# bldc_servo_controller_v1.net
KiCad netlist of a schematic drawn in EAGLE
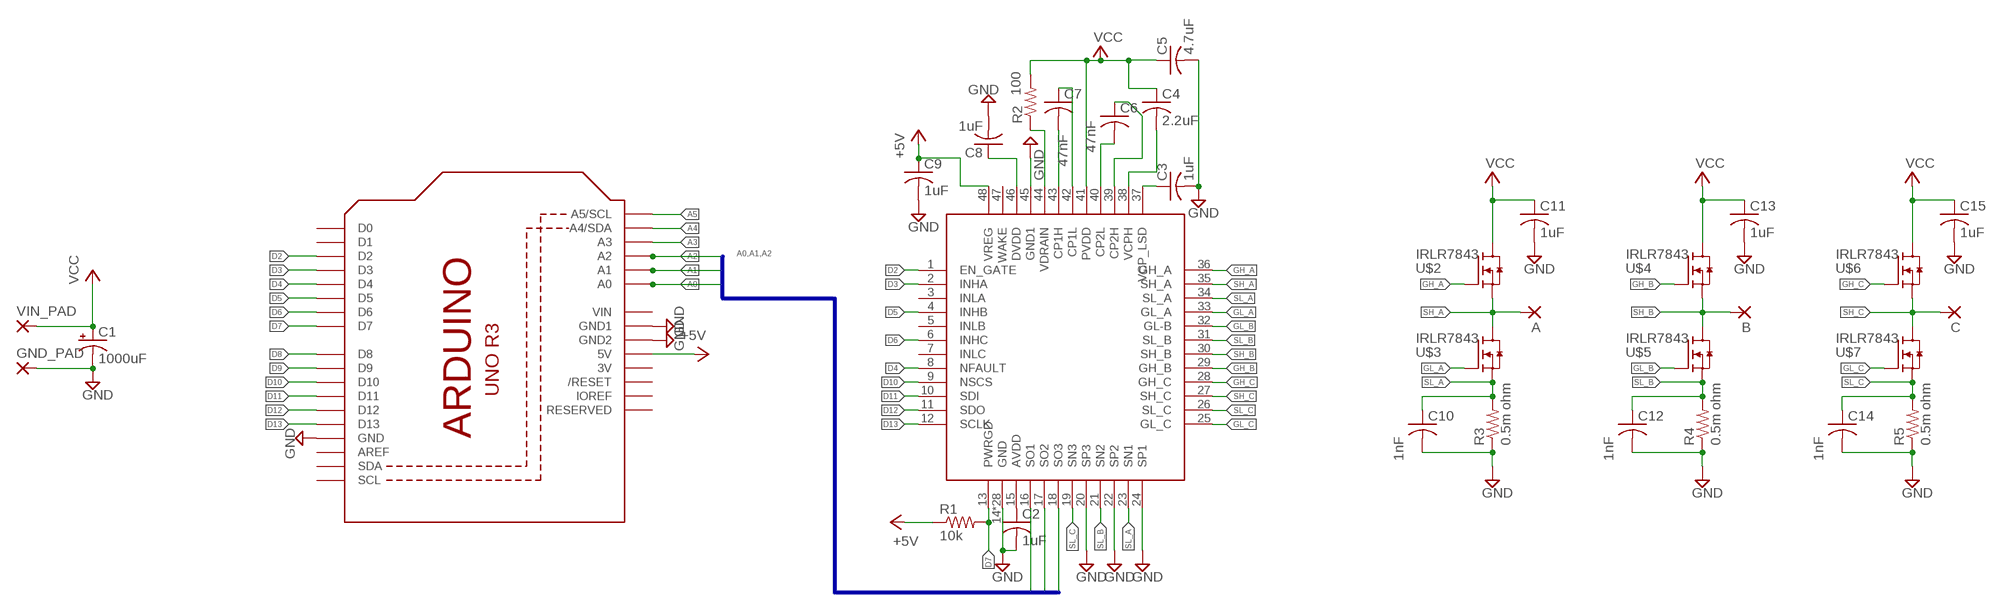
[diagram p0: schematic, sheet 1]

(export (version "E")
  (design (tool "Eeschema 10.0.6"))
  (components
    (comp (ref "A")
      (value "WIREPAD1,6/0,8")
      (footprint "eagle-import:1,6_0,8")
      (libsource (lib "eagle-import") (part "WIREPAD1,6/0,8"))
    )
    (comp (ref "B")
      (value "WIREPAD1,6/0,8")
      (footprint "eagle-import:1,6_0,8")
      (libsource (lib "eagle-import") (part "WIREPAD1,6/0,8"))
    )
    (comp (ref "C")
      (value "WIREPAD1,6/0,8")
      (footprint "eagle-import:1,6_0,8")
      (libsource (lib "eagle-import") (part "WIREPAD1,6/0,8"))
    )
    (comp (ref "C1")
      (value "1000uF")
      (footprint "eagle-import:E3,5-10")
      (libsource (lib "eagle-import") (part "CPOL-USE3.5-10"))
    )
    (comp (ref "C2")
      (value "1uF")
      (footprint "eagle-import:C0805")
      (libsource (lib "eagle-import") (part "C-USC0805"))
    )
    (comp (ref "C3")
      (value "1uF")
      (footprint "eagle-import:C0805")
      (libsource (lib "eagle-import") (part "C-USC0805"))
    )
    (comp (ref "C4")
      (value "2.2uF")
      (footprint "eagle-import:C0805")
      (libsource (lib "eagle-import") (part "C-USC0805"))
    )
    (comp (ref "C5")
      (value "4.7uF")
      (footprint "eagle-import:C0805")
      (libsource (lib "eagle-import") (part "C-USC0805"))
    )
    (comp (ref "C6")
      (value "47nF")
      (footprint "eagle-import:C0805")
      (libsource (lib "eagle-import") (part "C-USC0805"))
    )
    (comp (ref "C7")
      (value "47nF")
      (footprint "eagle-import:C0805")
      (libsource (lib "eagle-import") (part "C-USC0805"))
    )
    (comp (ref "C8")
      (value "1uF")
      (footprint "eagle-import:C0805")
      (libsource (lib "eagle-import") (part "C-USC0805"))
    )
    (comp (ref "C9")
      (value "1uF")
      (footprint "eagle-import:C0805")
      (libsource (lib "eagle-import") (part "C-USC0805"))
    )
    (comp (ref "C10")
      (value "1nF")
      (footprint "eagle-import:C0805")
      (libsource (lib "eagle-import") (part "C-USC0805"))
    )
    (comp (ref "C11")
      (value "1uF")
      (footprint "eagle-import:C0805")
      (libsource (lib "eagle-import") (part "C-USC0805"))
    )
    (comp (ref "C12")
      (value "1nF")
      (footprint "eagle-import:C0805")
      (libsource (lib "eagle-import") (part "C-USC0805"))
    )
    (comp (ref "C13")
      (value "1uF")
      (footprint "eagle-import:C0805")
      (libsource (lib "eagle-import") (part "C-USC0805"))
    )
    (comp (ref "C14")
      (value "1nF")
      (footprint "eagle-import:C0805")
      (libsource (lib "eagle-import") (part "C-USC0805"))
    )
    (comp (ref "C15")
      (value "1uF")
      (footprint "eagle-import:C0805")
      (libsource (lib "eagle-import") (part "C-USC0805"))
    )
    (comp (ref "GND_PAD")
      (value "WIREPAD1,6/0,8")
      (footprint "eagle-import:1,6_0,8")
      (libsource (lib "eagle-import") (part "WIREPAD1,6/0,8"))
    )
    (comp (ref "R1")
      (value "10k")
      (footprint "eagle-import:M0805")
      (libsource (lib "eagle-import") (part "R-US_M0805"))
    )
    (comp (ref "R2")
      (value "100")
      (footprint "eagle-import:M0805")
      (libsource (lib "eagle-import") (part "R-US_M0805"))
    )
    (comp (ref "R3")
      (value "0.5m ohm")
      (footprint "eagle-import:R2512")
      (libsource (lib "eagle-import") (part "R-US_R2512"))
    )
    (comp (ref "R4")
      (value "0.5m ohm")
      (footprint "eagle-import:R2512")
      (libsource (lib "eagle-import") (part "R-US_R2512"))
    )
    (comp (ref "R5")
      (value "0.5m ohm")
      (footprint "eagle-import:R2512")
      (libsource (lib "eagle-import") (part "R-US_R2512"))
    )
    (comp (ref "U$1")
      (value "DRV8305")
      (footprint "eagle-import:PFB_S-PQFP-G48")
      (libsource (lib "eagle-import") (part "DRV8305"))
    )
    (comp (ref "U$2")
      (value "IRLR7843")
      (footprint "eagle-import:TO252")
      (libsource (lib "eagle-import") (part "IRLR7843"))
    )
    (comp (ref "U$3")
      (value "IRLR7843")
      (footprint "eagle-import:TO252")
      (libsource (lib "eagle-import") (part "IRLR7843"))
    )
    (comp (ref "U$4")
      (value "IRLR7843")
      (footprint "eagle-import:TO252")
      (libsource (lib "eagle-import") (part "IRLR7843"))
    )
    (comp (ref "U$5")
      (value "IRLR7843")
      (footprint "eagle-import:TO252")
      (libsource (lib "eagle-import") (part "IRLR7843"))
    )
    (comp (ref "U$6")
      (value "IRLR7843")
      (footprint "eagle-import:TO252")
      (libsource (lib "eagle-import") (part "IRLR7843"))
    )
    (comp (ref "U$7")
      (value "IRLR7843")
      (footprint "eagle-import:TO252")
      (libsource (lib "eagle-import") (part "IRLR7843"))
    )
    (comp (ref "U1")
      (value "ARDUINOR3-BPLACE")
      (footprint "eagle-import:ARDUINOR3-BPLACE")
      (libsource (lib "eagle-import") (part "ARDUINOR3-BPLACE"))
    )
    (comp (ref "VIN_PAD")
      (value "WIREPAD1,6/0,8")
      (footprint "eagle-import:1,6_0,8")
      (libsource (lib "eagle-import") (part "WIREPAD1,6/0,8"))
    )
  )
  (nets
    (net (code "1") (name "+5V") (class "Default")
      (node (ref "C9") (pin "1") (pinfunction "1_1") (pintype "passive"))
      (node (ref "R1") (pin "1") (pinfunction "1_1") (pintype "passive"))
      (node (ref "U$1") (pin "48") (pinfunction "VREG_48") (pintype "bidirectional"))
      (node (ref "U1") (pin "5V") (pinfunction "5V_5V") (pintype "power_in"))
    )
    (net (code "2") (name "/3V") (class "Default")
      (node (ref "U1") (pin "3V") (pinfunction "3V_3V") (pintype "power_in"))
    )
    (net (code "3") (name "/VIN") (class "Default")
      (node (ref "U1") (pin "VIN") (pinfunction "VIN_VIN") (pintype "power_in"))
    )
    (net (code "4") (name "A0") (class "Default")
      (node (ref "U$1") (pin "16") (pinfunction "SO1_16") (pintype "bidirectional"))
      (node (ref "U1") (pin "A0") (pinfunction "A0_A0") (pintype "bidirectional"))
    )
    (net (code "5") (name "A1") (class "Default")
      (node (ref "U$1") (pin "17") (pinfunction "SO2_17") (pintype "bidirectional"))
      (node (ref "U1") (pin "A1") (pinfunction "A1_A1") (pintype "bidirectional"))
    )
    (net (code "6") (name "A2") (class "Default")
      (node (ref "U$1") (pin "18") (pinfunction "SO3_18") (pintype "bidirectional"))
      (node (ref "U1") (pin "A2") (pinfunction "A2_A2") (pintype "bidirectional"))
    )
    (net (code "7") (name "A3") (class "Default")
      (node (ref "U1") (pin "A3") (pinfunction "A3_A3") (pintype "bidirectional"))
    )
    (net (code "8") (name "A4") (class "Default")
      (node (ref "U1") (pin "A4") (pinfunction "A4/SDA_A4") (pintype "bidirectional"))
    )
    (net (code "9") (name "A5") (class "Default")
      (node (ref "U1") (pin "A5") (pinfunction "A5/SCL_A5") (pintype "bidirectional"))
    )
    (net (code "10") (name "D2") (class "Default")
      (node (ref "U$1") (pin "1") (pinfunction "EN_GATE_1") (pintype "bidirectional"))
      (node (ref "U1") (pin "D2") (pinfunction "D2_D2") (pintype "bidirectional"))
    )
    (net (code "11") (name "D3") (class "Default")
      (node (ref "U$1") (pin "2") (pinfunction "INHA_2") (pintype "bidirectional"))
      (node (ref "U1") (pin "D3") (pinfunction "D3_D3") (pintype "bidirectional"))
    )
    (net (code "12") (name "D4") (class "Default")
      (node (ref "U$1") (pin "8") (pinfunction "NFAULT_8") (pintype "bidirectional"))
      (node (ref "U1") (pin "D4") (pinfunction "D4_D4") (pintype "bidirectional"))
    )
    (net (code "13") (name "D5") (class "Default")
      (node (ref "U$1") (pin "4") (pinfunction "INHB_4") (pintype "bidirectional"))
      (node (ref "U1") (pin "D5") (pinfunction "D5_D5") (pintype "bidirectional"))
    )
    (net (code "14") (name "D6") (class "Default")
      (node (ref "U$1") (pin "6") (pinfunction "INHC_6") (pintype "bidirectional"))
      (node (ref "U1") (pin "D6") (pinfunction "D6_D6") (pintype "bidirectional"))
    )
    (net (code "15") (name "D7") (class "Default")
      (node (ref "R1") (pin "2") (pinfunction "2_2") (pintype "passive"))
      (node (ref "U$1") (pin "13") (pinfunction "PWRGD_13") (pintype "bidirectional"))
      (node (ref "U1") (pin "D7") (pinfunction "D7_D7") (pintype "bidirectional"))
    )
    (net (code "16") (name "D8") (class "Default")
      (node (ref "U1") (pin "D8") (pinfunction "D8_D8") (pintype "bidirectional"))
    )
    (net (code "17") (name "D9") (class "Default")
      (node (ref "U1") (pin "D9") (pinfunction "D9_D9") (pintype "bidirectional"))
    )
    (net (code "18") (name "D10") (class "Default")
      (node (ref "U$1") (pin "9") (pinfunction "NSCS_9") (pintype "bidirectional"))
      (node (ref "U1") (pin "D10") (pinfunction "D10_D10") (pintype "bidirectional"))
    )
    (net (code "19") (name "D11") (class "Default")
      (node (ref "U$1") (pin "10") (pinfunction "SDI_10") (pintype "bidirectional"))
      (node (ref "U1") (pin "D11") (pinfunction "D11_D11") (pintype "bidirectional"))
    )
    (net (code "20") (name "D12") (class "Default")
      (node (ref "U$1") (pin "11") (pinfunction "SDO_11") (pintype "bidirectional"))
      (node (ref "U1") (pin "D12") (pinfunction "D12_D12") (pintype "bidirectional"))
    )
    (net (code "21") (name "D13") (class "Default")
      (node (ref "U$1") (pin "12") (pinfunction "SCLK_12") (pintype "bidirectional"))
      (node (ref "U1") (pin "D13") (pinfunction "D13_D13") (pintype "bidirectional"))
    )
    (net (code "22") (name "GH_A") (class "Default")
      (node (ref "U$1") (pin "36") (pinfunction "GH_A_36") (pintype "bidirectional"))
      (node (ref "U$2") (pin "1") (pinfunction "G_1") (pintype "passive"))
    )
    (net (code "23") (name "GH_B") (class "Default")
      (node (ref "U$1") (pin "29") (pinfunction "GH_B_29") (pintype "bidirectional"))
      (node (ref "U$4") (pin "1") (pinfunction "G_1") (pintype "passive"))
    )
    (net (code "24") (name "GH_C") (class "Default")
      (node (ref "U$1") (pin "28") (pinfunction "GH_C_28") (pintype "bidirectional"))
      (node (ref "U$6") (pin "1") (pinfunction "G_1") (pintype "passive"))
    )
    (net (code "25") (name "GL_A") (class "Default")
      (node (ref "U$1") (pin "33") (pinfunction "GL_A_33") (pintype "bidirectional"))
      (node (ref "U$3") (pin "1") (pinfunction "G_1") (pintype "passive"))
    )
    (net (code "26") (name "GL_B") (class "Default")
      (node (ref "U$1") (pin "32") (pinfunction "GL-B_32") (pintype "bidirectional"))
      (node (ref "U$5") (pin "1") (pinfunction "G_1") (pintype "passive"))
    )
    (net (code "27") (name "GL_C") (class "Default")
      (node (ref "U$1") (pin "25") (pinfunction "GL_C_25") (pintype "bidirectional"))
      (node (ref "U$7") (pin "1") (pinfunction "G_1") (pintype "passive"))
    )
    (net (code "28") (name "GND") (class "Default")
      (node (ref "C1") (pin "-") (pinfunction "-_-") (pintype "passive"))
      (node (ref "C10") (pin "2") (pinfunction "2_2") (pintype "passive"))
      (node (ref "C11") (pin "2") (pinfunction "2_2") (pintype "passive"))
      (node (ref "C12") (pin "2") (pinfunction "2_2") (pintype "passive"))
      (node (ref "C13") (pin "2") (pinfunction "2_2") (pintype "passive"))
      (node (ref "C14") (pin "2") (pinfunction "2_2") (pintype "passive"))
      (node (ref "C15") (pin "2") (pinfunction "2_2") (pintype "passive"))
      (node (ref "C2") (pin "2") (pinfunction "2_2") (pintype "passive"))
      (node (ref "C3") (pin "2") (pinfunction "2_2") (pintype "passive"))
      (node (ref "C5") (pin "2") (pinfunction "2_2") (pintype "passive"))
      (node (ref "C8") (pin "2") (pinfunction "2_2") (pintype "passive"))
      (node (ref "C9") (pin "2") (pinfunction "2_2") (pintype "passive"))
      (node (ref "GND_PAD") (pin "1") (pinfunction "P_1") (pintype "passive"))
      (node (ref "R3") (pin "1") (pinfunction "1_1") (pintype "passive"))
      (node (ref "R4") (pin "1") (pinfunction "1_1") (pintype "passive"))
      (node (ref "R5") (pin "1") (pinfunction "1_1") (pintype "passive"))
      (node (ref "U$1") (pin "14") (pinfunction "GND_14") (pintype "bidirectional"))
      (node (ref "U$1") (pin "20") (pinfunction "SP3_20") (pintype "bidirectional"))
      (node (ref "U$1") (pin "22") (pinfunction "SP2_22") (pintype "bidirectional"))
      (node (ref "U$1") (pin "24") (pinfunction "SP1_24") (pintype "bidirectional"))
      (node (ref "U$1") (pin "45") (pinfunction "GND1_45") (pintype "bidirectional"))
      (node (ref "U$1") (pin "P$1") (pinfunction "GND_P$1") (pintype "bidirectional"))
      (node (ref "U$1") (pin "P$10") (pinfunction "GND_P$10") (pintype "bidirectional"))
      (node (ref "U$1") (pin "P$11") (pinfunction "GND_P$11") (pintype "bidirectional"))
      (node (ref "U$1") (pin "P$12") (pinfunction "GND_P$12") (pintype "bidirectional"))
      (node (ref "U$1") (pin "P$13") (pinfunction "GND_P$13") (pintype "bidirectional"))
      (node (ref "U$1") (pin "P$14") (pinfunction "GND_P$14") (pintype "bidirectional"))
      (node (ref "U$1") (pin "P$15") (pinfunction "GND_P$15") (pintype "bidirectional"))
      (node (ref "U$1") (pin "P$16") (pinfunction "GND_P$16") (pintype "bidirectional"))
      (node (ref "U$1") (pin "P$17") (pinfunction "GND_P$17") (pintype "bidirectional"))
      (node (ref "U$1") (pin "P$18") (pinfunction "GND_P$18") (pintype "bidirectional"))
      (node (ref "U$1") (pin "P$19") (pinfunction "GND_P$19") (pintype "bidirectional"))
      (node (ref "U$1") (pin "P$2") (pinfunction "GND_P$2") (pintype "bidirectional"))
      (node (ref "U$1") (pin "P$20") (pinfunction "GND_P$20") (pintype "bidirectional"))
      (node (ref "U$1") (pin "P$21") (pinfunction "GND_P$21") (pintype "bidirectional"))
      (node (ref "U$1") (pin "P$22") (pinfunction "GND_P$22") (pintype "bidirectional"))
      (node (ref "U$1") (pin "P$23") (pinfunction "GND_P$23") (pintype "bidirectional"))
      (node (ref "U$1") (pin "P$24") (pinfunction "GND_P$24") (pintype "bidirectional"))
      (node (ref "U$1") (pin "P$25") (pinfunction "GND_P$25") (pintype "bidirectional"))
      (node (ref "U$1") (pin "P$26") (pinfunction "GND_P$26") (pintype "bidirectional"))
      (node (ref "U$1") (pin "P$27") (pinfunction "GND_P$27") (pintype "bidirectional"))
      (node (ref "U$1") (pin "P$3") (pinfunction "GND_P$3") (pintype "bidirectional"))
      (node (ref "U$1") (pin "P$4") (pinfunction "GND_P$4") (pintype "bidirectional"))
      (node (ref "U$1") (pin "P$5") (pinfunction "GND_P$5") (pintype "bidirectional"))
      (node (ref "U$1") (pin "P$6") (pinfunction "GND_P$6") (pintype "bidirectional"))
      (node (ref "U$1") (pin "P$7") (pinfunction "GND_P$7") (pintype "bidirectional"))
      (node (ref "U$1") (pin "P$8") (pinfunction "GND_P$8") (pintype "bidirectional"))
      (node (ref "U$1") (pin "P$9") (pinfunction "GND_P$9") (pintype "bidirectional"))
      (node (ref "U1") (pin "GND") (pinfunction "GND_GND") (pintype "power_in"))
      (node (ref "U1") (pin "GND1") (pinfunction "GND1_GND1") (pintype "power_in"))
      (node (ref "U1") (pin "GND2") (pinfunction "GND2_GND2") (pintype "power_in"))
    )
    (net (code "29") (name "Net-(U$1-AVDD)") (class "Default")
      (node (ref "C2") (pin "1") (pinfunction "1_1") (pintype "passive"))
      (node (ref "U$1") (pin "15") (pinfunction "AVDD_15") (pintype "bidirectional"))
    )
    (net (code "30") (name "Net-(U$1-CP1H)") (class "Default")
      (node (ref "C7") (pin "2") (pinfunction "2_2") (pintype "passive"))
      (node (ref "U$1") (pin "43") (pinfunction "CP1H_43") (pintype "bidirectional"))
    )
    (net (code "31") (name "Net-(U$1-CP1L)") (class "Default")
      (node (ref "C7") (pin "1") (pinfunction "1_1") (pintype "passive"))
      (node (ref "U$1") (pin "42") (pinfunction "CP1L_42") (pintype "bidirectional"))
    )
    (net (code "32") (name "Net-(U$1-CP2H)") (class "Default")
      (node (ref "C6") (pin "1") (pinfunction "1_1") (pintype "passive"))
      (node (ref "U$1") (pin "39") (pinfunction "CP2H_39") (pintype "bidirectional"))
    )
    (net (code "33") (name "Net-(U$1-CP2L)") (class "Default")
      (node (ref "C6") (pin "2") (pinfunction "2_2") (pintype "passive"))
      (node (ref "U$1") (pin "40") (pinfunction "CP2L_40") (pintype "bidirectional"))
    )
    (net (code "34") (name "Net-(U$1-DVDD)") (class "Default")
      (node (ref "C8") (pin "1") (pinfunction "1_1") (pintype "passive"))
      (node (ref "U$1") (pin "46") (pinfunction "DVDD_46") (pintype "bidirectional"))
    )
    (net (code "35") (name "Net-(U$1-VCPH)") (class "Default")
      (node (ref "C4") (pin "2") (pinfunction "2_2") (pintype "passive"))
      (node (ref "U$1") (pin "38") (pinfunction "VCPH_38") (pintype "bidirectional"))
    )
    (net (code "36") (name "Net-(U$1-VCP_LSD)") (class "Default")
      (node (ref "C3") (pin "1") (pinfunction "1_1") (pintype "passive"))
      (node (ref "U$1") (pin "37") (pinfunction "VCP_LSD_37") (pintype "bidirectional"))
    )
    (net (code "37") (name "Net-(U$1-VDRAIN)") (class "Default")
      (node (ref "R2") (pin "1") (pinfunction "1_1") (pintype "passive"))
      (node (ref "U$1") (pin "44") (pinfunction "VDRAIN_44") (pintype "bidirectional"))
    )
    (net (code "38") (name "SH_A") (class "Default")
      (node (ref "A") (pin "1") (pinfunction "P_1") (pintype "passive"))
      (node (ref "U$1") (pin "35") (pinfunction "SH_A_35") (pintype "bidirectional"))
      (node (ref "U$2") (pin "2") (pinfunction "S_2") (pintype "passive"))
      (node (ref "U$3") (pin "3") (pinfunction "D_3") (pintype "passive"))
    )
    (net (code "39") (name "SH_B") (class "Default")
      (node (ref "B") (pin "1") (pinfunction "P_1") (pintype "passive"))
      (node (ref "U$1") (pin "30") (pinfunction "SH_B_30") (pintype "bidirectional"))
      (node (ref "U$4") (pin "2") (pinfunction "S_2") (pintype "passive"))
      (node (ref "U$5") (pin "3") (pinfunction "D_3") (pintype "passive"))
    )
    (net (code "40") (name "SH_C") (class "Default")
      (node (ref "C") (pin "1") (pinfunction "P_1") (pintype "passive"))
      (node (ref "U$1") (pin "27") (pinfunction "SH_C_27") (pintype "bidirectional"))
      (node (ref "U$6") (pin "2") (pinfunction "S_2") (pintype "passive"))
      (node (ref "U$7") (pin "3") (pinfunction "D_3") (pintype "passive"))
    )
    (net (code "41") (name "SL_A") (class "Default")
      (node (ref "C10") (pin "1") (pinfunction "1_1") (pintype "passive"))
      (node (ref "R3") (pin "2") (pinfunction "2_2") (pintype "passive"))
      (node (ref "U$1") (pin "23") (pinfunction "SN1_23") (pintype "bidirectional"))
      (node (ref "U$1") (pin "34") (pinfunction "SL_A_34") (pintype "bidirectional"))
      (node (ref "U$3") (pin "2") (pinfunction "S_2") (pintype "passive"))
    )
    (net (code "42") (name "SL_B") (class "Default")
      (node (ref "C12") (pin "1") (pinfunction "1_1") (pintype "passive"))
      (node (ref "R4") (pin "2") (pinfunction "2_2") (pintype "passive"))
      (node (ref "U$1") (pin "21") (pinfunction "SN2_21") (pintype "bidirectional"))
      (node (ref "U$1") (pin "31") (pinfunction "SL_B_31") (pintype "bidirectional"))
      (node (ref "U$5") (pin "2") (pinfunction "S_2") (pintype "passive"))
    )
    (net (code "43") (name "SL_C") (class "Default")
      (node (ref "C14") (pin "1") (pinfunction "1_1") (pintype "passive"))
      (node (ref "R5") (pin "2") (pinfunction "2_2") (pintype "passive"))
      (node (ref "U$1") (pin "19") (pinfunction "SN3_19") (pintype "bidirectional"))
      (node (ref "U$1") (pin "26") (pinfunction "SL_C_26") (pintype "bidirectional"))
      (node (ref "U$7") (pin "2") (pinfunction "S_2") (pintype "passive"))
    )
    (net (code "44") (name "VCC") (class "Default")
      (node (ref "C1") (pin "+") (pinfunction "+_+") (pintype "passive"))
      (node (ref "C11") (pin "1") (pinfunction "1_1") (pintype "passive"))
      (node (ref "C13") (pin "1") (pinfunction "1_1") (pintype "passive"))
      (node (ref "C15") (pin "1") (pinfunction "1_1") (pintype "passive"))
      (node (ref "C4") (pin "1") (pinfunction "1_1") (pintype "passive"))
      (node (ref "C5") (pin "1") (pinfunction "1_1") (pintype "passive"))
      (node (ref "R2") (pin "2") (pinfunction "2_2") (pintype "passive"))
      (node (ref "U$1") (pin "41") (pinfunction "PVDD_41") (pintype "bidirectional"))
      (node (ref "U$2") (pin "3") (pinfunction "D_3") (pintype "passive"))
      (node (ref "U$4") (pin "3") (pinfunction "D_3") (pintype "passive"))
      (node (ref "U$6") (pin "3") (pinfunction "D_3") (pintype "passive"))
      (node (ref "VIN_PAD") (pin "1") (pinfunction "P_1") (pintype "passive"))
    )
    (net (code "45") (name "unconnected-(U$1-INLA-Pad3)") (class "Default")
      (node (ref "U$1") (pin "3") (pinfunction "INLA_3") (pintype "bidirectional"))
    )
    (net (code "46") (name "unconnected-(U$1-INLB-Pad5)") (class "Default")
      (node (ref "U$1") (pin "5") (pinfunction "INLB_5") (pintype "bidirectional"))
    )
    (net (code "47") (name "unconnected-(U$1-INLC-Pad7)") (class "Default")
      (node (ref "U$1") (pin "7") (pinfunction "INLC_7") (pintype "bidirectional"))
    )
    (net (code "48") (name "unconnected-(U$1-WAKE-Pad47)") (class "Default")
      (node (ref "U$1") (pin "47") (pinfunction "WAKE_47") (pintype "bidirectional"))
    )
    (net (code "49") (name "unconnected-(U1-PadAREF)") (class "Default")
      (node (ref "U1") (pin "AREF") (pinfunction "AREF_AREF") (pintype "bidirectional"))
    )
    (net (code "50") (name "unconnected-(U1-PadD0)") (class "Default")
      (node (ref "U1") (pin "D0") (pinfunction "D0_D0") (pintype "bidirectional"))
    )
    (net (code "51") (name "unconnected-(U1-PadD1)") (class "Default")
      (node (ref "U1") (pin "D1") (pinfunction "D1_D1") (pintype "bidirectional"))
    )
    (net (code "52") (name "unconnected-(U1-PadIOREF)") (class "Default")
      (node (ref "U1") (pin "IOREF") (pinfunction "IOREF_IOREF") (pintype "output"))
    )
    (net (code "53") (name "unconnected-(U1-PadRESERVED)") (class "Default")
      (node (ref "U1") (pin "RESERVED") (pinfunction "RESERVED_RESERVED") (pintype "no_connect"))
    )
    (net (code "54") (name "unconnected-(U1-PadSCL)") (class "Default")
      (node (ref "U1") (pin "SCL") (pinfunction "SCL_SCL") (pintype "bidirectional"))
    )
    (net (code "55") (name "unconnected-(U1-PadSDA)") (class "Default")
      (node (ref "U1") (pin "SDA") (pinfunction "SDA_SDA") (pintype "bidirectional"))
    )
    (net (code "56") (name "unconnected-(U1-{slash}RESET-PadRESET)") (class "Default")
      (node (ref "U1") (pin "RESET") (pinfunction "/RESET_RESET") (pintype "bidirectional"))
    )
  )
)
